# MicroSpecSensorBoard_Connectors_V2_1.net
KiCad netlist of a schematic drawn in Altium Designer
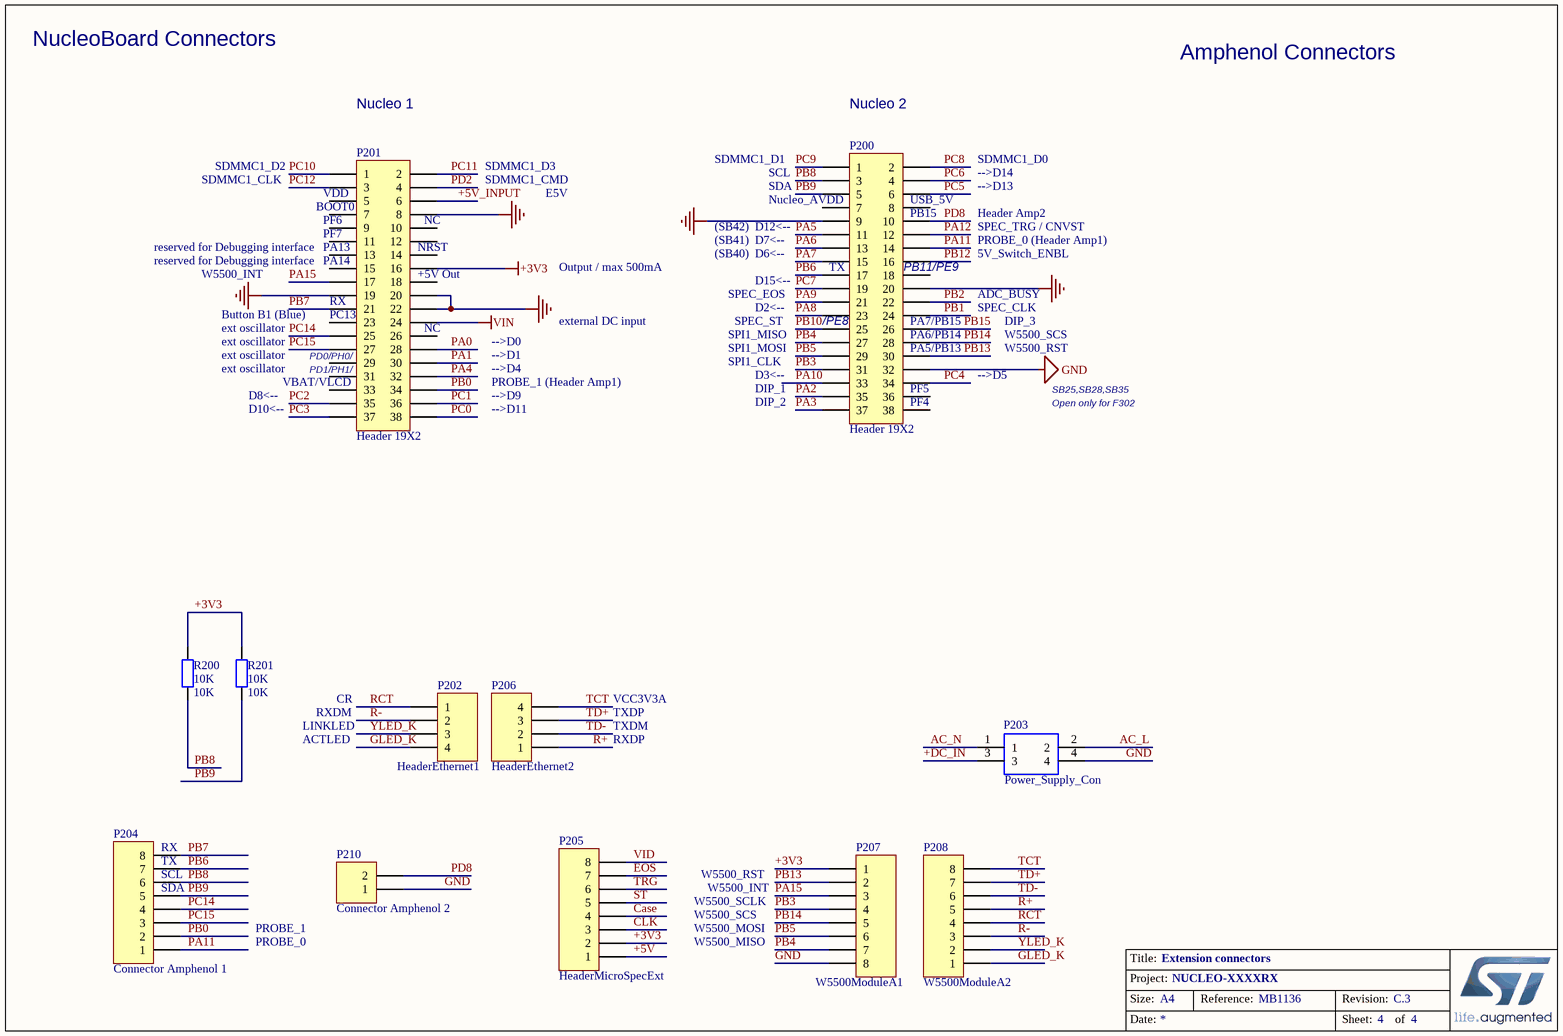
[diagram p0: MicroSpecSensorBoard_Connectors_V2_1.SchDoc]

(export (version "E")
  (design (tool "Eeschema 10.0.6"))
  (components
    (comp (ref "P200")
      (value "Header 19X2")
      (footprint "HDR2X19")
      (description "Header, 19-Pin, Dual row")
      (fields (field (name "PUBLISHER") "Altium Limited"))
      (libsource (lib "Miscellaneous Connectors") (part "Header 19X2"))
    )
    (comp (ref "P201")
      (value "Header 19X2")
      (footprint "HDR2X19")
      (description "Header, 19-Pin, Dual row")
      (fields (field (name "PUBLISHER") "Altium Limited"))
      (libsource (lib "Miscellaneous Connectors") (part "Header 19X2"))
    )
    (comp (ref "P202")
      (value "HeaderEthernet1")
      (footprint "HDR1X4")
      (description "Header, 4-Pin")
      (fields (field (name "PUBLISHER") "Altium Limited"))
      (libsource (lib "") (part "Header 4_1"))
    )
    (comp (ref "P203")
      (value "Power_Supply_Con")
      (footprint "1864053")
      (fields (field (name "RS PART NUMBER") "1113745") (field (name "MANUFACTURER_PART_NUMBER") "1864053"))
      (libsource (lib "USER_Library") (part "1864053"))
    )
    (comp (ref "P204")
      (value "Connector Amphenol 1")
      (footprint "HDR1X8 - phoenix")
      (description "Header, 8-Pin Phönix Contact")
      (fields (field (name "PUBLISHER") "Altium Limited"))
      (libsource (lib "USER_Library") (part "MHDR1X8"))
    )
    (comp (ref "P205")
      (value "HeaderMicroSpecExt")
      (footprint "HDR1X8")
      (description "Header, 8-Pin")
      (fields (field (name "PUBLISHER") "Altium Limited"))
      (libsource (lib "Miscellaneous Connectors") (part "Header 8"))
    )
    (comp (ref "P206")
      (value "HeaderEthernet2")
      (footprint "HDR1X4")
      (description "Header, 4-Pin")
      (fields (field (name "PUBLISHER") "Altium Limited"))
      (libsource (lib "Miscellaneous Connectors") (part "Header 4"))
    )
    (comp (ref "P207")
      (value "W5500ModuleA1")
      (footprint "HDR1X8")
      (description "Header, 8-Pin")
      (fields (field (name "PUBLISHER") "Altium Limited"))
      (libsource (lib "") (part "Header 8_1"))
    )
    (comp (ref "P208")
      (value "W5500ModuleA2")
      (footprint "HDR1X8")
      (description "Header, 8-Pin")
      (fields (field (name "PUBLISHER") "Altium Limited"))
      (libsource (lib "Miscellaneous Connectors") (part "Header 8"))
    )
    (comp (ref "P210")
      (value "Connector Amphenol 2")
      (footprint "HDR1X2 - phoenix")
      (description "Header, 2-Pin, MKDSN1,5 / 2, Phönix Contact")
      (fields (field (name "PUBLISHER") "UFZ Leipzig"))
      (libsource (lib "USER_Library") (part "MHDR1X2"))
    )
    (comp (ref "R200")
      (value "10K")
      (footprint "6-0805_L")
      (description "Resistor")
      (fields (field (name "ALTIUM_VALUE") "10K") (field (name "PUBLISHER") "Altium Limited"))
      (libsource (lib "USER_Library") (part "Res2"))
    )
    (comp (ref "R201")
      (value "10K")
      (footprint "6-0805_L")
      (description "Resistor")
      (fields (field (name "ALTIUM_VALUE") "10K") (field (name "PUBLISHER") "Altium Limited"))
      (libsource (lib "USER_Library") (part "Res2"))
    )
  )
  (nets
    (net (code "1") (name "+3V3") (class "Default")
      (node (ref "P201") (pin "16") (pinfunction "16_16") (pintype "passive"))
      (node (ref "P205") (pin "2") (pinfunction "2_2") (pintype "passive"))
      (node (ref "P207") (pin "1") (pinfunction "1_1") (pintype "passive"))
      (node (ref "R200") (pin "2") (pinfunction "2_2") (pintype "passive"))
      (node (ref "R201") (pin "2") (pinfunction "2_2") (pintype "passive"))
    )
    (net (code "2") (name "/+5V") (class "Default")
      (node (ref "P205") (pin "1") (pinfunction "1_1") (pintype "passive"))
    )
    (net (code "3") (name "/+5V_INPUT") (class "Default")
      (node (ref "P201") (pin "6") (pinfunction "6_6") (pintype "passive"))
    )
    (net (code "4") (name "/+DC_IN") (class "Default")
      (node (ref "P203") (pin "3") (pinfunction "3_3") (pintype "passive"))
    )
    (net (code "5") (name "/AC_L") (class "Default")
      (node (ref "P203") (pin "2") (pinfunction "2_2") (pintype "passive"))
    )
    (net (code "6") (name "/AC_N") (class "Default")
      (node (ref "P203") (pin "1") (pinfunction "1_1") (pintype "passive"))
    )
    (net (code "7") (name "/CLK") (class "Default")
      (node (ref "P205") (pin "3") (pinfunction "3_3") (pintype "passive"))
    )
    (net (code "8") (name "/Case") (class "Default")
      (node (ref "P205") (pin "4") (pinfunction "4_4") (pintype "passive"))
    )
    (net (code "9") (name "/EOS") (class "Default")
      (node (ref "P205") (pin "7") (pinfunction "7_7") (pintype "passive"))
    )
    (net (code "10") (name "/GLED_K") (class "Default")
      (node (ref "P202") (pin "4") (pinfunction "4_4") (pintype "passive"))
      (node (ref "P208") (pin "1") (pinfunction "1_1") (pintype "passive"))
    )
    (net (code "11") (name "/PA0") (class "Default")
      (node (ref "P201") (pin "28") (pinfunction "28_28") (pintype "passive"))
    )
    (net (code "12") (name "/PA1") (class "Default")
      (node (ref "P201") (pin "30") (pinfunction "30_30") (pintype "passive"))
    )
    (net (code "13") (name "/PA2") (class "Default")
      (node (ref "P200") (pin "35") (pinfunction "35_35") (pintype "passive"))
    )
    (net (code "14") (name "/PA3") (class "Default")
      (node (ref "P200") (pin "37") (pinfunction "37_37") (pintype "passive"))
    )
    (net (code "15") (name "/PA4") (class "Default")
      (node (ref "P201") (pin "32") (pinfunction "32_32") (pintype "passive"))
    )
    (net (code "16") (name "/PA5") (class "Default")
      (node (ref "P200") (pin "11") (pinfunction "11_11") (pintype "passive"))
    )
    (net (code "17") (name "/PA6") (class "Default")
      (node (ref "P200") (pin "13") (pinfunction "13_13") (pintype "passive"))
    )
    (net (code "18") (name "/PA7") (class "Default")
      (node (ref "P200") (pin "15") (pinfunction "15_15") (pintype "passive"))
    )
    (net (code "19") (name "/PA8") (class "Default")
      (node (ref "P200") (pin "23") (pinfunction "23_23") (pintype "passive"))
    )
    (net (code "20") (name "/PA9") (class "Default")
      (node (ref "P200") (pin "21") (pinfunction "21_21") (pintype "passive"))
    )
    (net (code "21") (name "/PA10") (class "Default")
      (node (ref "P200") (pin "33") (pinfunction "33_33") (pintype "passive"))
    )
    (net (code "22") (name "/PA11") (class "Default")
      (node (ref "P200") (pin "14") (pinfunction "14_14") (pintype "passive"))
      (node (ref "P204") (pin "1") (pinfunction "1_1") (pintype "passive"))
    )
    (net (code "23") (name "/PA12") (class "Default")
      (node (ref "P200") (pin "12") (pinfunction "12_12") (pintype "passive"))
    )
    (net (code "24") (name "/PA15") (class "Default")
      (node (ref "P201") (pin "17") (pinfunction "17_17") (pintype "passive"))
      (node (ref "P207") (pin "3") (pinfunction "3_3") (pintype "passive"))
    )
    (net (code "25") (name "/PB0") (class "Default")
      (node (ref "P201") (pin "34") (pinfunction "34_34") (pintype "passive"))
      (node (ref "P204") (pin "2") (pinfunction "2_2") (pintype "passive"))
    )
    (net (code "26") (name "/PB1") (class "Default")
      (node (ref "P200") (pin "24") (pinfunction "24_24") (pintype "passive"))
    )
    (net (code "27") (name "/PB2") (class "Default")
      (node (ref "P200") (pin "22") (pinfunction "22_22") (pintype "passive"))
    )
    (net (code "28") (name "/PB3") (class "Default")
      (node (ref "P200") (pin "31") (pinfunction "31_31") (pintype "passive"))
      (node (ref "P207") (pin "4") (pinfunction "4_4") (pintype "passive"))
    )
    (net (code "29") (name "/PB4") (class "Default")
      (node (ref "P200") (pin "27") (pinfunction "27_27") (pintype "passive"))
      (node (ref "P207") (pin "7") (pinfunction "7_7") (pintype "passive"))
    )
    (net (code "30") (name "/PB5") (class "Default")
      (node (ref "P200") (pin "29") (pinfunction "29_29") (pintype "passive"))
      (node (ref "P207") (pin "6") (pinfunction "6_6") (pintype "passive"))
    )
    (net (code "31") (name "/PB6") (class "Default")
      (node (ref "P200") (pin "17") (pinfunction "17_17") (pintype "passive"))
      (node (ref "P204") (pin "7") (pinfunction "7_7") (pintype "passive"))
    )
    (net (code "32") (name "/PB7") (class "Default")
      (node (ref "P201") (pin "21") (pinfunction "21_21") (pintype "passive"))
      (node (ref "P204") (pin "8") (pinfunction "8_8") (pintype "passive"))
    )
    (net (code "33") (name "/PB8") (class "Default")
      (node (ref "P200") (pin "3") (pinfunction "3_3") (pintype "passive"))
      (node (ref "P204") (pin "6") (pinfunction "6_6") (pintype "passive"))
      (node (ref "R200") (pin "1") (pinfunction "1_1") (pintype "passive"))
    )
    (net (code "34") (name "/PB9") (class "Default")
      (node (ref "P200") (pin "5") (pinfunction "5_5") (pintype "passive"))
      (node (ref "P204") (pin "5") (pinfunction "5_5") (pintype "passive"))
      (node (ref "R201") (pin "1") (pinfunction "1_1") (pintype "passive"))
    )
    (net (code "35") (name "/PB10") (class "Default")
      (node (ref "P200") (pin "25") (pinfunction "25_25") (pintype "passive"))
    )
    (net (code "36") (name "/PB12") (class "Default")
      (node (ref "P200") (pin "16") (pinfunction "16_16") (pintype "passive"))
    )
    (net (code "37") (name "/PB13") (class "Default")
      (node (ref "P200") (pin "30") (pinfunction "30_30") (pintype "passive"))
      (node (ref "P207") (pin "2") (pinfunction "2_2") (pintype "passive"))
    )
    (net (code "38") (name "/PB14") (class "Default")
      (node (ref "P200") (pin "28") (pinfunction "28_28") (pintype "passive"))
      (node (ref "P207") (pin "5") (pinfunction "5_5") (pintype "passive"))
    )
    (net (code "39") (name "/PB15") (class "Default")
      (node (ref "P200") (pin "26") (pinfunction "26_26") (pintype "passive"))
    )
    (net (code "40") (name "/PC0") (class "Default")
      (node (ref "P201") (pin "38") (pinfunction "38_38") (pintype "passive"))
    )
    (net (code "41") (name "/PC1") (class "Default")
      (node (ref "P201") (pin "36") (pinfunction "36_36") (pintype "passive"))
    )
    (net (code "42") (name "/PC2") (class "Default")
      (node (ref "P201") (pin "35") (pinfunction "35_35") (pintype "passive"))
    )
    (net (code "43") (name "/PC3") (class "Default")
      (node (ref "P201") (pin "37") (pinfunction "37_37") (pintype "passive"))
    )
    (net (code "44") (name "/PC4") (class "Default")
      (node (ref "P200") (pin "34") (pinfunction "34_34") (pintype "passive"))
    )
    (net (code "45") (name "/PC5") (class "Default")
      (node (ref "P200") (pin "6") (pinfunction "6_6") (pintype "passive"))
    )
    (net (code "46") (name "/PC6") (class "Default")
      (node (ref "P200") (pin "4") (pinfunction "4_4") (pintype "passive"))
    )
    (net (code "47") (name "/PC7") (class "Default")
      (node (ref "P200") (pin "19") (pinfunction "19_19") (pintype "passive"))
    )
    (net (code "48") (name "/PC8") (class "Default")
      (node (ref "P200") (pin "2") (pinfunction "2_2") (pintype "passive"))
    )
    (net (code "49") (name "/PC9") (class "Default")
      (node (ref "P200") (pin "1") (pinfunction "1_1") (pintype "passive"))
    )
    (net (code "50") (name "/PC10") (class "Default")
      (node (ref "P201") (pin "1") (pinfunction "1_1") (pintype "passive"))
    )
    (net (code "51") (name "/PC11") (class "Default")
      (node (ref "P201") (pin "2") (pinfunction "2_2") (pintype "passive"))
    )
    (net (code "52") (name "/PC12") (class "Default")
      (node (ref "P201") (pin "3") (pinfunction "3_3") (pintype "passive"))
    )
    (net (code "53") (name "/PC14") (class "Default")
      (node (ref "P201") (pin "25") (pinfunction "25_25") (pintype "passive"))
      (node (ref "P204") (pin "4") (pinfunction "4_4") (pintype "passive"))
    )
    (net (code "54") (name "/PC15") (class "Default")
      (node (ref "P201") (pin "27") (pinfunction "27_27") (pintype "passive"))
      (node (ref "P204") (pin "3") (pinfunction "3_3") (pintype "passive"))
    )
    (net (code "55") (name "/PD2") (class "Default")
      (node (ref "P201") (pin "4") (pinfunction "4_4") (pintype "passive"))
    )
    (net (code "56") (name "/PD8") (class "Default")
      (node (ref "P200") (pin "10") (pinfunction "10_10") (pintype "passive"))
      (node (ref "P210") (pin "2") (pinfunction "2_2") (pintype "passive"))
    )
    (net (code "57") (name "/R+") (class "Default")
      (node (ref "P206") (pin "1") (pinfunction "1_1") (pintype "passive"))
      (node (ref "P208") (pin "5") (pinfunction "5_5") (pintype "passive"))
    )
    (net (code "58") (name "/R-") (class "Default")
      (node (ref "P202") (pin "2") (pinfunction "2_2") (pintype "passive"))
      (node (ref "P208") (pin "3") (pinfunction "3_3") (pintype "passive"))
    )
    (net (code "59") (name "/RCT") (class "Default")
      (node (ref "P202") (pin "1") (pinfunction "1_1") (pintype "passive"))
      (node (ref "P208") (pin "4") (pinfunction "4_4") (pintype "passive"))
    )
    (net (code "60") (name "/ST") (class "Default")
      (node (ref "P205") (pin "5") (pinfunction "5_5") (pintype "passive"))
    )
    (net (code "61") (name "/TCT") (class "Default")
      (node (ref "P206") (pin "4") (pinfunction "4_4") (pintype "passive"))
      (node (ref "P208") (pin "8") (pinfunction "8_8") (pintype "passive"))
    )
    (net (code "62") (name "/TD+") (class "Default")
      (node (ref "P206") (pin "3") (pinfunction "3_3") (pintype "passive"))
      (node (ref "P208") (pin "7") (pinfunction "7_7") (pintype "passive"))
    )
    (net (code "63") (name "/TD-") (class "Default")
      (node (ref "P206") (pin "2") (pinfunction "2_2") (pintype "passive"))
      (node (ref "P208") (pin "6") (pinfunction "6_6") (pintype "passive"))
    )
    (net (code "64") (name "/TRG") (class "Default")
      (node (ref "P205") (pin "6") (pinfunction "6_6") (pintype "passive"))
    )
    (net (code "65") (name "/VID") (class "Default")
      (node (ref "P205") (pin "8") (pinfunction "8_8") (pintype "passive"))
    )
    (net (code "66") (name "/YLED_K") (class "Default")
      (node (ref "P202") (pin "3") (pinfunction "3_3") (pintype "passive"))
      (node (ref "P208") (pin "2") (pinfunction "2_2") (pintype "passive"))
    )
    (net (code "67") (name "GND") (class "Default")
      (node (ref "P200") (pin "20") (pinfunction "20_20") (pintype "passive"))
      (node (ref "P200") (pin "32") (pinfunction "32_32") (pintype "passive"))
      (node (ref "P200") (pin "9") (pinfunction "9_9") (pintype "passive"))
      (node (ref "P201") (pin "19") (pinfunction "19_19") (pintype "passive"))
      (node (ref "P201") (pin "20") (pinfunction "20_20") (pintype "passive"))
      (node (ref "P201") (pin "22") (pinfunction "22_22") (pintype "passive"))
      (node (ref "P201") (pin "8") (pinfunction "8_8") (pintype "passive"))
      (node (ref "P203") (pin "4") (pinfunction "4_4") (pintype "passive"))
      (node (ref "P207") (pin "8") (pinfunction "8_8") (pintype "passive"))
      (node (ref "P210") (pin "1") (pinfunction "1_1") (pintype "passive"))
    )
    (net (code "68") (name "VIN") (class "Default")
      (node (ref "P201") (pin "24") (pinfunction "24_24") (pintype "passive"))
    )
    (net (code "69") (name "unconnected-(P200-Pad7)") (class "Default")
      (node (ref "P200") (pin "7") (pinfunction "7_7") (pintype "passive"))
    )
    (net (code "70") (name "unconnected-(P200-Pad8)") (class "Default")
      (node (ref "P200") (pin "8") (pinfunction "8_8") (pintype "passive"))
    )
    (net (code "71") (name "unconnected-(P200-Pad18)") (class "Default")
      (node (ref "P200") (pin "18") (pinfunction "18_18") (pintype "passive"))
    )
    (net (code "72") (name "unconnected-(P200-Pad36)") (class "Default")
      (node (ref "P200") (pin "36") (pinfunction "36_36") (pintype "passive"))
    )
    (net (code "73") (name "unconnected-(P200-Pad38)") (class "Default")
      (node (ref "P200") (pin "38") (pinfunction "38_38") (pintype "passive"))
    )
    (net (code "74") (name "unconnected-(P201-Pad5)") (class "Default")
      (node (ref "P201") (pin "5") (pinfunction "5_5") (pintype "passive"))
    )
    (net (code "75") (name "unconnected-(P201-Pad7)") (class "Default")
      (node (ref "P201") (pin "7") (pinfunction "7_7") (pintype "passive"))
    )
    (net (code "76") (name "unconnected-(P201-Pad9)") (class "Default")
      (node (ref "P201") (pin "9") (pinfunction "9_9") (pintype "passive"))
    )
    (net (code "77") (name "unconnected-(P201-Pad10)") (class "Default")
      (node (ref "P201") (pin "10") (pinfunction "10_10") (pintype "passive"))
    )
    (net (code "78") (name "unconnected-(P201-Pad11)") (class "Default")
      (node (ref "P201") (pin "11") (pinfunction "11_11") (pintype "passive"))
    )
    (net (code "79") (name "unconnected-(P201-Pad12)") (class "Default")
      (node (ref "P201") (pin "12") (pinfunction "12_12") (pintype "passive"))
    )
    (net (code "80") (name "unconnected-(P201-Pad13)") (class "Default")
      (node (ref "P201") (pin "13") (pinfunction "13_13") (pintype "passive"))
    )
    (net (code "81") (name "unconnected-(P201-Pad14)") (class "Default")
      (node (ref "P201") (pin "14") (pinfunction "14_14") (pintype "passive"))
    )
    (net (code "82") (name "unconnected-(P201-Pad15)") (class "Default")
      (node (ref "P201") (pin "15") (pinfunction "15_15") (pintype "passive"))
    )
    (net (code "83") (name "unconnected-(P201-Pad18)") (class "Default")
      (node (ref "P201") (pin "18") (pinfunction "18_18") (pintype "passive"))
    )
    (net (code "84") (name "unconnected-(P201-Pad23)") (class "Default")
      (node (ref "P201") (pin "23") (pinfunction "23_23") (pintype "passive"))
    )
    (net (code "85") (name "unconnected-(P201-Pad26)") (class "Default")
      (node (ref "P201") (pin "26") (pinfunction "26_26") (pintype "passive"))
    )
    (net (code "86") (name "unconnected-(P201-Pad29)") (class "Default")
      (node (ref "P201") (pin "29") (pinfunction "29_29") (pintype "passive"))
    )
    (net (code "87") (name "unconnected-(P201-Pad31)") (class "Default")
      (node (ref "P201") (pin "31") (pinfunction "31_31") (pintype "passive"))
    )
    (net (code "88") (name "unconnected-(P201-Pad33)") (class "Default")
      (node (ref "P201") (pin "33") (pinfunction "33_33") (pintype "passive"))
    )
  )
)
